# Interface_Mikrobus.net
KiCad netlist of a schematic drawn in Altium Designer
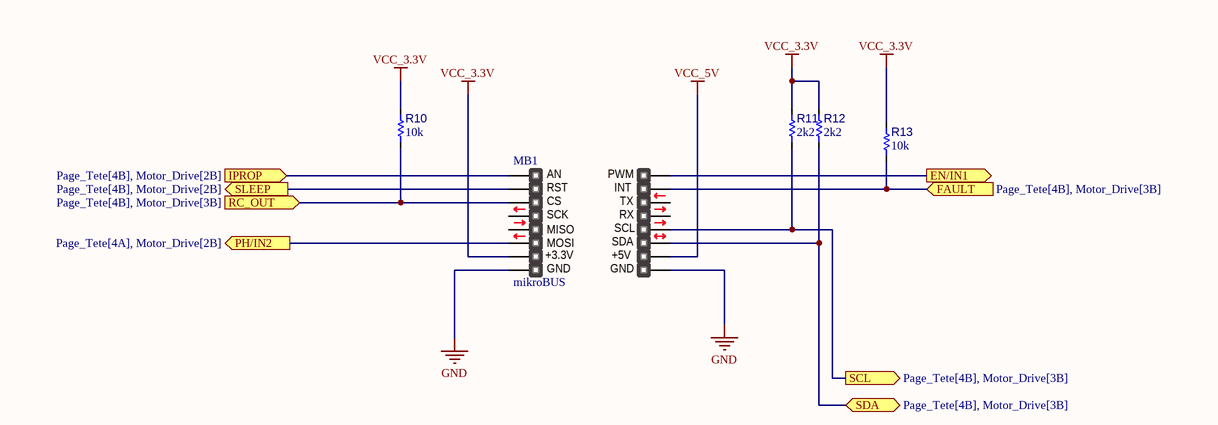
[diagram p0: Interface_Mikrobus.SchDoc]

(export (version "E")
  (design (tool "Eeschema 10.0.6"))
  (components
    (comp (ref "MB1")
      (value "mikroBUS")
      (footprint "mikroBUS - Large")
      (description "mikroBUS compatible add-on board")
      (libsource (lib "mikroBUS_Add-on_standard") (part "mikroBUS compatible add-on board"))
    )
    (comp (ref "R10")
      (value "10k")
      (footprint "R_1005[0402]")
      (description "Resistor type 1")
      (fields (field (name "TOLERANCE") "1%") (field (name "Comment") "Res 10k 1% 0402"))
      (libsource (lib "243-436-MikoBus-DrvMot") (part "resistor"))
    )
    (comp (ref "R11")
      (value "2k2")
      (footprint "R_1005[0402]")
      (description "Resistor type 1")
      (fields (field (name "TOLERANCE") "1%") (field (name "Comment") "Res 2k2 1% 0402"))
      (libsource (lib "243-436-MikoBus-DrvMot") (part "resistor"))
    )
    (comp (ref "R12")
      (value "2k2")
      (footprint "R_1005[0402]")
      (description "Resistor type 1")
      (fields (field (name "TOLERANCE") "1%") (field (name "Comment") "Res 2k2 1% 0402"))
      (libsource (lib "243-436-MikoBus-DrvMot") (part "resistor"))
    )
    (comp (ref "R13")
      (value "10k")
      (footprint "R_1005[0402]")
      (description "Resistor type 1")
      (fields (field (name "TOLERANCE") "1%") (field (name "Comment") "Res 10k 1% 0402"))
      (libsource (lib "243-436-MikoBus-DrvMot") (part "resistor"))
    )
  )
  (nets
    (net (code "1") (name "/EN{slash}IN1") (class "Default")
      (node (ref "MB1") (pin "16") (pinfunction "PWM_16") (pintype "passive"))
    )
    (net (code "2") (name "/FAULT") (class "Default")
      (node (ref "MB1") (pin "15") (pinfunction "INT_15") (pintype "passive"))
      (node (ref "R13") (pin "1") (pinfunction "1_1") (pintype "passive"))
    )
    (net (code "3") (name "/IPROP") (class "Default")
      (node (ref "MB1") (pin "1") (pinfunction "AN_1") (pintype "passive"))
    )
    (net (code "4") (name "/PH{slash}IN2") (class "Default")
      (node (ref "MB1") (pin "6") (pinfunction "MOSI_6") (pintype "passive"))
    )
    (net (code "5") (name "/RC_OUT") (class "Default")
      (node (ref "MB1") (pin "3") (pinfunction "CS_3") (pintype "passive"))
      (node (ref "R10") (pin "1") (pinfunction "1_1") (pintype "passive"))
    )
    (net (code "6") (name "/SCL") (class "Default")
      (node (ref "MB1") (pin "12") (pinfunction "SCL_12") (pintype "passive"))
      (node (ref "R11") (pin "1") (pinfunction "1_1") (pintype "passive"))
    )
    (net (code "7") (name "/SDA") (class "Default")
      (node (ref "MB1") (pin "11") (pinfunction "SDA_11") (pintype "passive"))
      (node (ref "R12") (pin "1") (pinfunction "1_1") (pintype "passive"))
    )
    (net (code "8") (name "/SLEEP") (class "Default")
      (node (ref "MB1") (pin "2") (pinfunction "RST_2") (pintype "passive"))
    )
    (net (code "9") (name "GND") (class "Default")
      (node (ref "MB1") (pin "8") (pinfunction "GND_8") (pintype "passive"))
      (node (ref "MB1") (pin "9") (pinfunction "GND_9") (pintype "passive"))
    )
    (net (code "10") (name "VCC_3.3V") (class "Default")
      (node (ref "MB1") (pin "7") (pinfunction "3.3V_7") (pintype "passive"))
      (node (ref "R10") (pin "2") (pinfunction "2_2") (pintype "passive"))
      (node (ref "R11") (pin "2") (pinfunction "2_2") (pintype "passive"))
      (node (ref "R12") (pin "2") (pinfunction "2_2") (pintype "passive"))
      (node (ref "R13") (pin "2") (pinfunction "2_2") (pintype "passive"))
    )
    (net (code "11") (name "VCC_5V") (class "Default")
      (node (ref "MB1") (pin "10") (pinfunction "5V_10") (pintype "passive"))
    )
    (net (code "12") (name "unconnected-(MB1-MISO-Pad5)") (class "Default")
      (node (ref "MB1") (pin "5") (pinfunction "MISO_5") (pintype "passive"))
    )
    (net (code "13") (name "unconnected-(MB1-RX-Pad14)") (class "Default")
      (node (ref "MB1") (pin "14") (pinfunction "RX_14") (pintype "passive"))
    )
    (net (code "14") (name "unconnected-(MB1-SCK-Pad4)") (class "Default")
      (node (ref "MB1") (pin "4") (pinfunction "SCK_4") (pintype "passive"))
    )
    (net (code "15") (name "unconnected-(MB1-TX-Pad13)") (class "Default")
      (node (ref "MB1") (pin "13") (pinfunction "TX_13") (pintype "passive"))
    )
  )
)
